# 07_Mute.net
KiCad netlist of a schematic drawn in Altium Designer
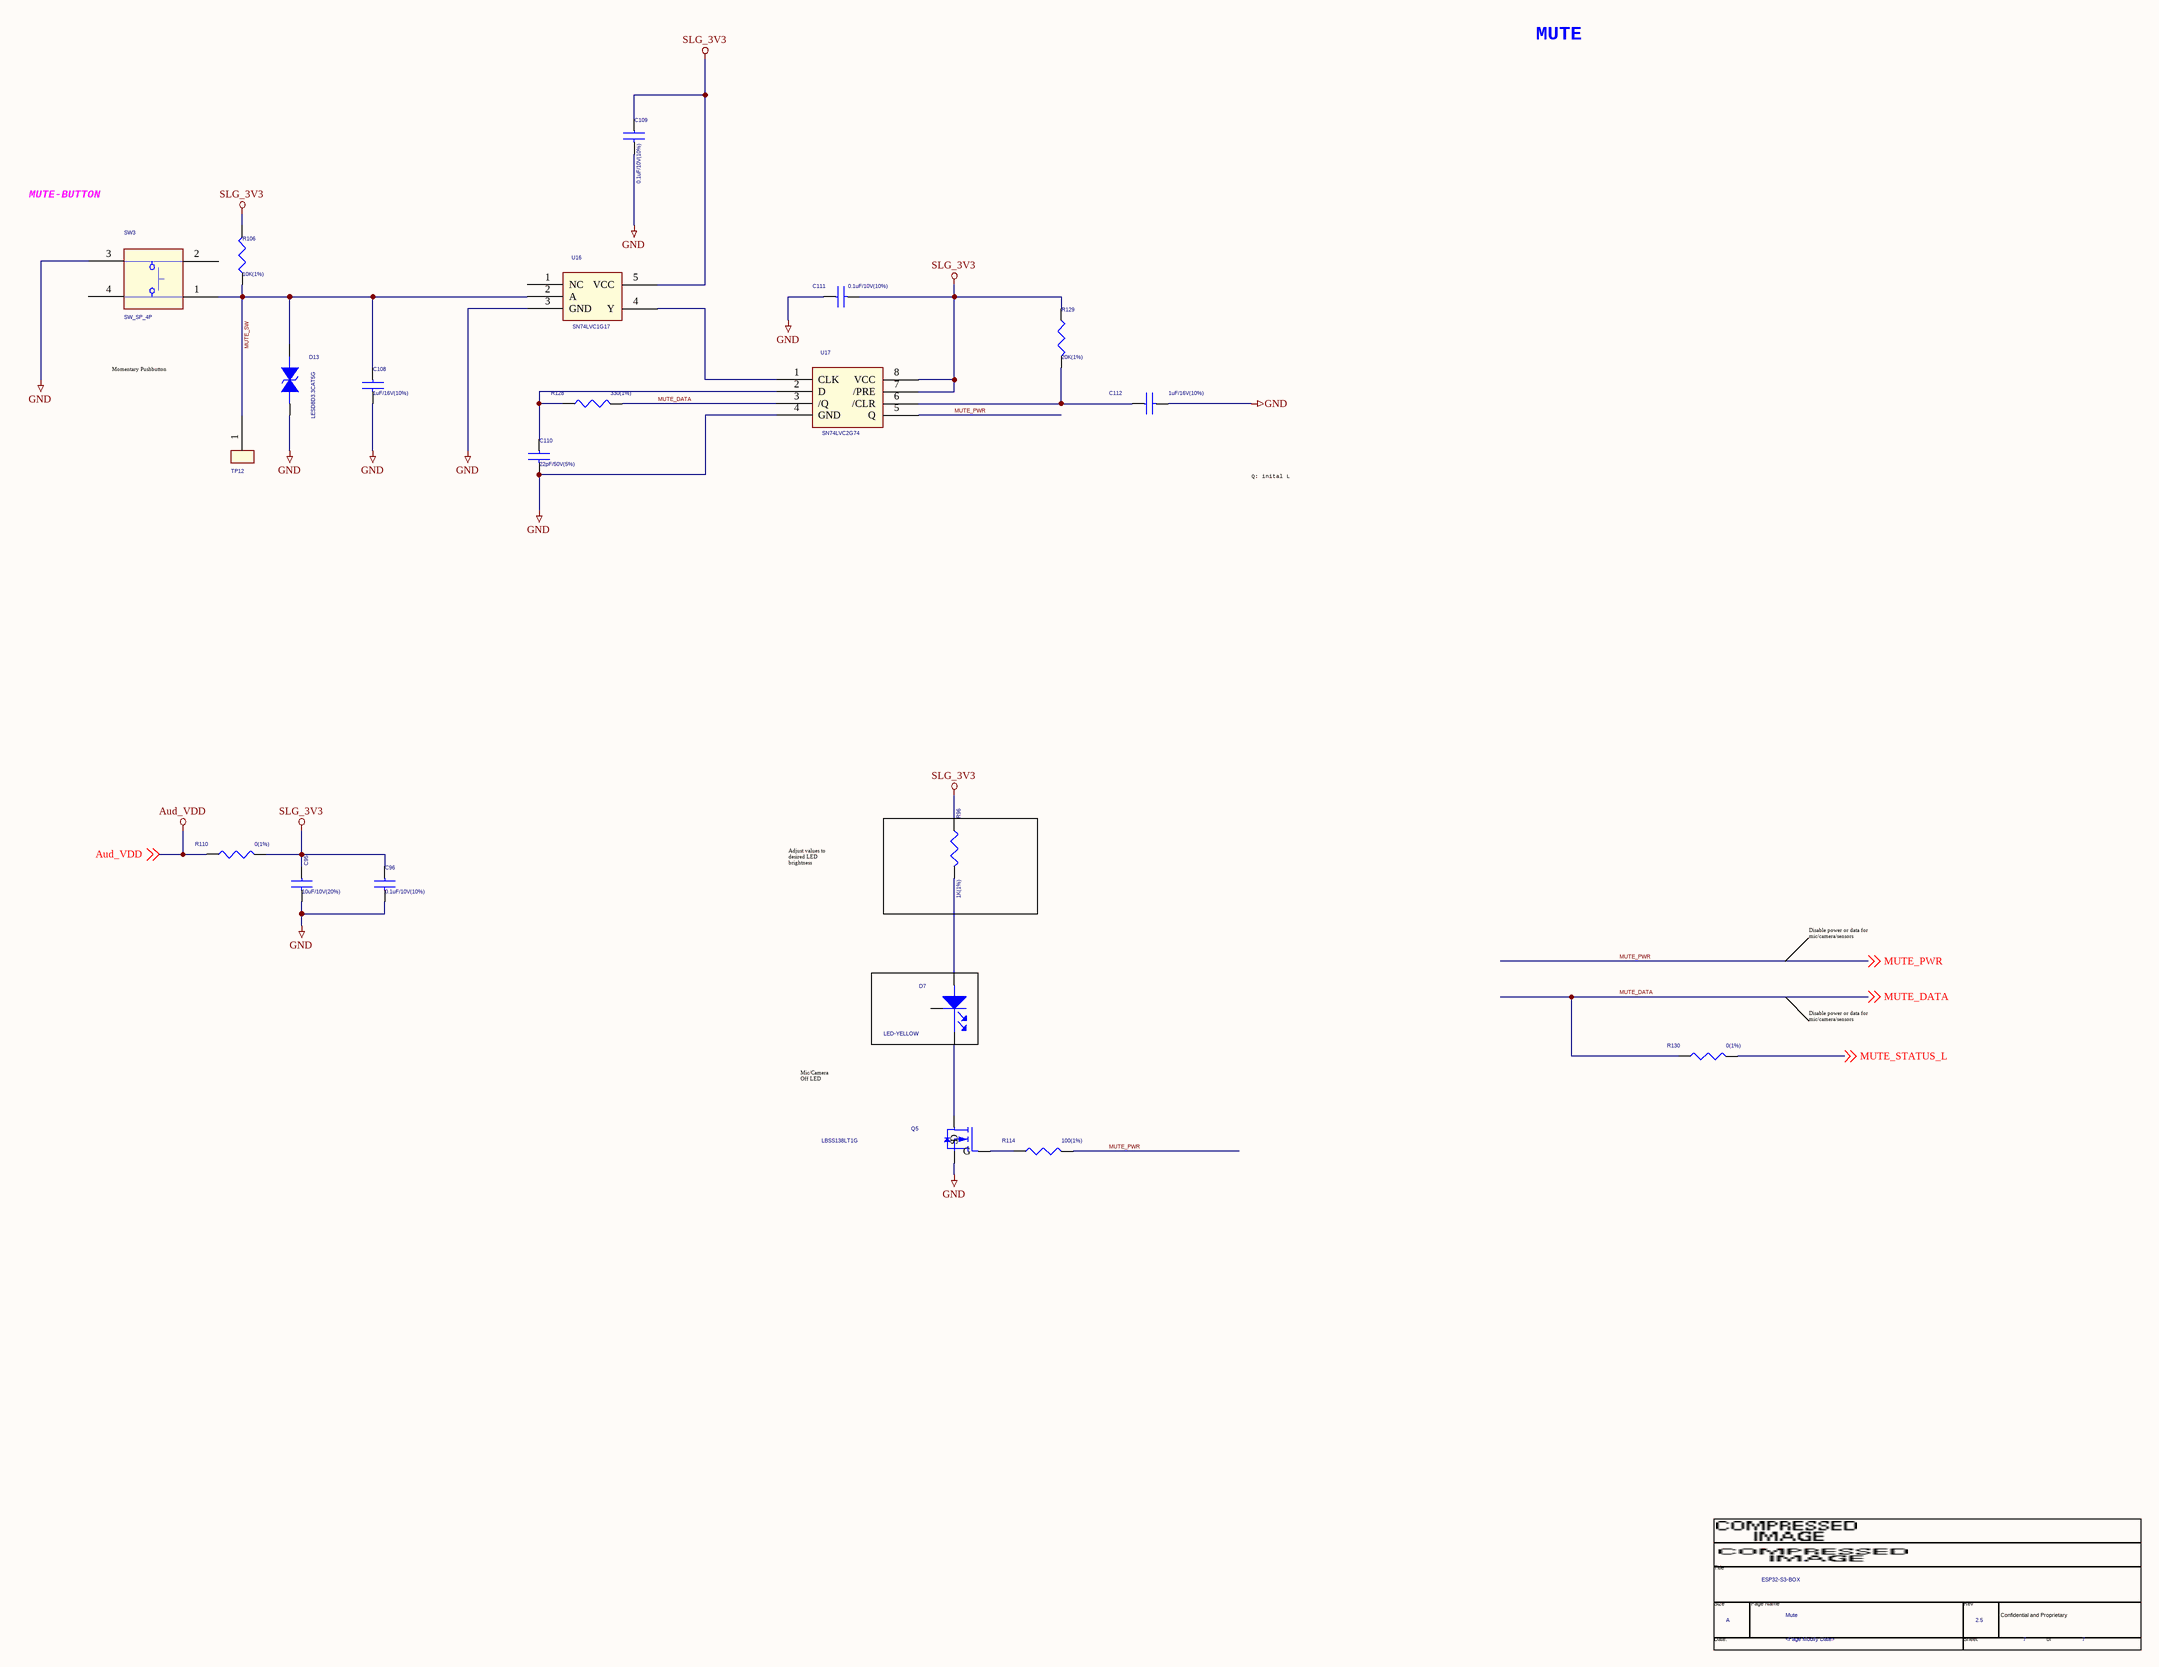
[diagram p0: 07_Mute.SchDoc]

(export (version "E")
  (design (tool "Eeschema 10.0.6"))
  (components
    (comp (ref "C95")
      (value "10uF/10V(20%)")
      (footprint "C0402")
      (fields (field (name "PART NUMBER") "ES11047103700000"))
      (libsource (lib "*") (part "CAPACITOR"))
    )
    (comp (ref "C96")
      (value "0.1uF/10V(10%)")
      (footprint "C0201")
      (fields (field (name "PART NUMBER") "ES11025103610001"))
      (libsource (lib "*") (part "CAPACITOR"))
    )
    (comp (ref "C108")
      (value "1uF/16V(10%)")
      (footprint "C0402")
      (fields (field (name "PART NUMBER") "ES11046104610000"))
      (libsource (lib "*") (part "CAPACITOR"))
    )
    (comp (ref "C109")
      (value "0.1uF/10V(10%)")
      (footprint "C0402")
      (fields (field (name "PART NUMBER") "ES11045103620000"))
      (libsource (lib "*") (part "CAPACITOR"))
    )
    (comp (ref "C110")
      (value "22pF/50V(5%)")
      (footprint "C0402")
      (fields (field (name "PART NUMBER") "ES11041226520001"))
      (libsource (lib "*") (part "CAPACITOR"))
    )
    (comp (ref "C111")
      (value "0.1uF/10V(10%)")
      (footprint "C0402")
      (fields (field (name "PART NUMBER") "ES11045103620000"))
      (libsource (lib "*") (part "CAPACITOR"))
    )
    (comp (ref "C112")
      (value "1uF/16V(10%)")
      (footprint "C0402")
      (fields (field (name "PART NUMBER") "ES11046104610000"))
      (libsource (lib "*") (part "CAPACITOR"))
    )
    (comp (ref "D7") (value "LED-YELLOW") (footprint "LED_SMD1206") (libsource (lib "*") (part "LED-BLUE")))
    (comp (ref "D13")
      (value "LESD8D3.3CAT5G")
      (footprint "SOD882")
      (fields (field (name "PART NUMBER") "ES31320010000000"))
      (libsource (lib "*") (part "DIODE_BI_DIR"))
    )
    (comp (ref "Q5")
      (value "LBSS138LT1G")
      (footprint "SOT23-3")
      (fields (field (name "PART NUMBER") "ES31440030000000"))
      (libsource (lib "*") (part "NMOS"))
    )
    (comp (ref "R96")
      (value "1K(1%)")
      (footprint "R0201")
      (fields (field (name "PART NUMBER") "ES21023100000001"))
      (libsource (lib "*") (part "RESISTOR"))
    )
    (comp (ref "R106")
      (value "10K(1%)")
      (footprint "R0201")
      (fields (field (name "PART NUMBER") "ES21024100000001"))
      (libsource (lib "*") (part "RESISTOR"))
    )
    (comp (ref "R110")
      (value "0(1%)")
      (footprint "R0402")
      (fields (field (name "PART NUMBER") "ES21040000000001"))
      (libsource (lib "*") (part "RESISTOR"))
    )
    (comp (ref "R114")
      (value "100(1%)")
      (footprint "R0201")
      (fields (field (name "PART NUMBER") "ES21022100000001"))
      (libsource (lib "*") (part "RESISTOR"))
    )
    (comp (ref "R128") (value "330(1%)") (footprint "R0402") (libsource (lib "*") (part "RESISTOR")))
    (comp (ref "R129")
      (value "20K(1%)")
      (footprint "R0402")
      (fields (field (name "PART NUMBER") "ES21044200000001"))
      (libsource (lib "*") (part "RESISTOR"))
    )
    (comp (ref "R130")
      (value "0(1%)")
      (footprint "R0402")
      (fields (field (name "PART NUMBER") "ES21040000000001"))
      (libsource (lib "*") (part "RESISTOR"))
    )
    (comp (ref "SW3")
      (value "SW_SP_4P")
      (footprint "SW4-3X3P5X1P1-SMT")
      (libsource (lib "*") (part "SW_SP_4P"))
    )
    (comp (ref "TP12")
      (value "TESTPOINT")
      (footprint "TPC_D40")
      (fields (field (name "PART NUMBER") "ES51990010000000"))
      (libsource (lib "*") (part "TESTPOINT"))
    )
    (comp (ref "U16")
      (value "SN74LVC1G17")
      (footprint "SOT23-5-S")
      (libsource (lib "*") (part "SN74LVC1G17"))
    )
    (comp (ref "U17") (value "SN74LVC2G74") (footprint "VSSOP8") (libsource (lib "*") (part "SN74LVC2G74")))
  )
  (nets
    (net (code "1") (name "/MUTE_SW") (class "Default")
      (node (ref "C108") (pin "1") (pinfunction "1_1") (pintype "passive"))
      (node (ref "D13") (pin "2") (pinfunction "2_2") (pintype "passive"))
      (node (ref "R106") (pin "1") (pinfunction "1_1") (pintype "passive"))
      (node (ref "SW3") (pin "1") (pinfunction "1_1") (pintype "passive"))
      (node (ref "TP12") (pin "1") (pinfunction "1_1") (pintype "passive"))
      (node (ref "U16") (pin "2") (pinfunction "A_2") (pintype "passive"))
    )
    (net (code "2") (name "Aud_VDD") (class "Default")
      (node (ref "R110") (pin "1") (pinfunction "1_1") (pintype "passive"))
    )
    (net (code "3") (name "GND") (class "Default")
      (node (ref "C108") (pin "2") (pinfunction "2_2") (pintype "passive"))
      (node (ref "C109") (pin "2") (pinfunction "2_2") (pintype "passive"))
      (node (ref "C110") (pin "2") (pinfunction "2_2") (pintype "passive"))
      (node (ref "C111") (pin "1") (pinfunction "1_1") (pintype "passive"))
      (node (ref "C112") (pin "2") (pinfunction "2_2") (pintype "passive"))
      (node (ref "C95") (pin "2") (pinfunction "2_2") (pintype "passive"))
      (node (ref "C96") (pin "2") (pinfunction "2_2") (pintype "passive"))
      (node (ref "D13") (pin "1") (pinfunction "1_1") (pintype "passive"))
      (node (ref "Q5") (pin "2") (pinfunction "S_2") (pintype "passive"))
      (node (ref "SW3") (pin "3") (pinfunction "3_3") (pintype "passive"))
      (node (ref "U16") (pin "3") (pinfunction "GND_3") (pintype "passive"))
      (node (ref "U17") (pin "4") (pinfunction "GND_4") (pintype "passive"))
    )
    (net (code "4") (name "MUTE_DATA") (class "Default")
      (node (ref "R128") (pin "2") (pinfunction "2_2") (pintype "passive"))
      (node (ref "R130") (pin "1") (pinfunction "1_1") (pintype "passive"))
      (node (ref "U17") (pin "3") (pinfunction "/Q_3") (pintype "passive"))
    )
    (net (code "5") (name "MUTE_PWR") (class "Default")
      (node (ref "R114") (pin "2") (pinfunction "2_2") (pintype "passive"))
      (node (ref "U17") (pin "5") (pinfunction "Q_5") (pintype "passive"))
    )
    (net (code "6") (name "MUTE_STATUS_L") (class "Default")
      (node (ref "R130") (pin "2") (pinfunction "2_2") (pintype "passive"))
    )
    (net (code "7") (name "Net-(D7-Pad1)") (class "Default")
      (node (ref "D7") (pin "1") (pinfunction "1_1") (pintype "passive"))
      (node (ref "R96") (pin "1") (pinfunction "1_1") (pintype "passive"))
    )
    (net (code "8") (name "Net-(Q5-D)") (class "Default")
      (node (ref "D7") (pin "2") (pinfunction "2_2") (pintype "passive"))
      (node (ref "Q5") (pin "3") (pinfunction "D_3") (pintype "passive"))
    )
    (net (code "9") (name "Net-(Q5-G)") (class "Default")
      (node (ref "Q5") (pin "1") (pinfunction "G_1") (pintype "passive"))
      (node (ref "R114") (pin "1") (pinfunction "1_1") (pintype "passive"))
    )
    (net (code "10") (name "Net-(U16-Y)") (class "Default")
      (node (ref "U16") (pin "4") (pinfunction "Y_4") (pintype "passive"))
      (node (ref "U17") (pin "1") (pinfunction "CLK_1") (pintype "passive"))
    )
    (net (code "11") (name "Net-(U17-D)") (class "Default")
      (node (ref "C110") (pin "1") (pinfunction "1_1") (pintype "passive"))
      (node (ref "R128") (pin "1") (pinfunction "1_1") (pintype "passive"))
      (node (ref "U17") (pin "2") (pinfunction "D_2") (pintype "passive"))
    )
    (net (code "12") (name "Net-(U17-{slash}CLR)") (class "Default")
      (node (ref "C112") (pin "1") (pinfunction "1_1") (pintype "passive"))
      (node (ref "R129") (pin "2") (pinfunction "2_2") (pintype "passive"))
      (node (ref "U17") (pin "6") (pinfunction "/CLR_6") (pintype "passive"))
    )
    (net (code "13") (name "SLG_3V3") (class "Default")
      (node (ref "C109") (pin "1") (pinfunction "1_1") (pintype "passive"))
      (node (ref "C111") (pin "2") (pinfunction "2_2") (pintype "passive"))
      (node (ref "C95") (pin "1") (pinfunction "1_1") (pintype "passive"))
      (node (ref "C96") (pin "1") (pinfunction "1_1") (pintype "passive"))
      (node (ref "R106") (pin "2") (pinfunction "2_2") (pintype "passive"))
      (node (ref "R110") (pin "2") (pinfunction "2_2") (pintype "passive"))
      (node (ref "R129") (pin "1") (pinfunction "1_1") (pintype "passive"))
      (node (ref "R96") (pin "2") (pinfunction "2_2") (pintype "passive"))
      (node (ref "U16") (pin "5") (pinfunction "VCC_5") (pintype "passive"))
      (node (ref "U17") (pin "7") (pinfunction "/PRE_7") (pintype "passive"))
      (node (ref "U17") (pin "8") (pinfunction "VCC_8") (pintype "passive"))
    )
    (net (code "14") (name "unconnected-(D7-Pad3)") (class "Default")
      (node (ref "D7") (pin "3") (pinfunction "3_3") (pintype "passive"))
    )
    (net (code "15") (name "unconnected-(SW3-Pad2)") (class "Default")
      (node (ref "SW3") (pin "2") (pinfunction "2_2") (pintype "passive"))
    )
    (net (code "16") (name "unconnected-(SW3-Pad4)") (class "Default")
      (node (ref "SW3") (pin "4") (pinfunction "4_4") (pintype "passive"))
    )
    (net (code "17") (name "unconnected-(U16-NC-Pad1)") (class "Default")
      (node (ref "U16") (pin "1") (pinfunction "NC_1") (pintype "passive"))
    )
  )
)
